# PS2_Regulators.net
KiCad netlist of a schematic drawn in Altium Designer
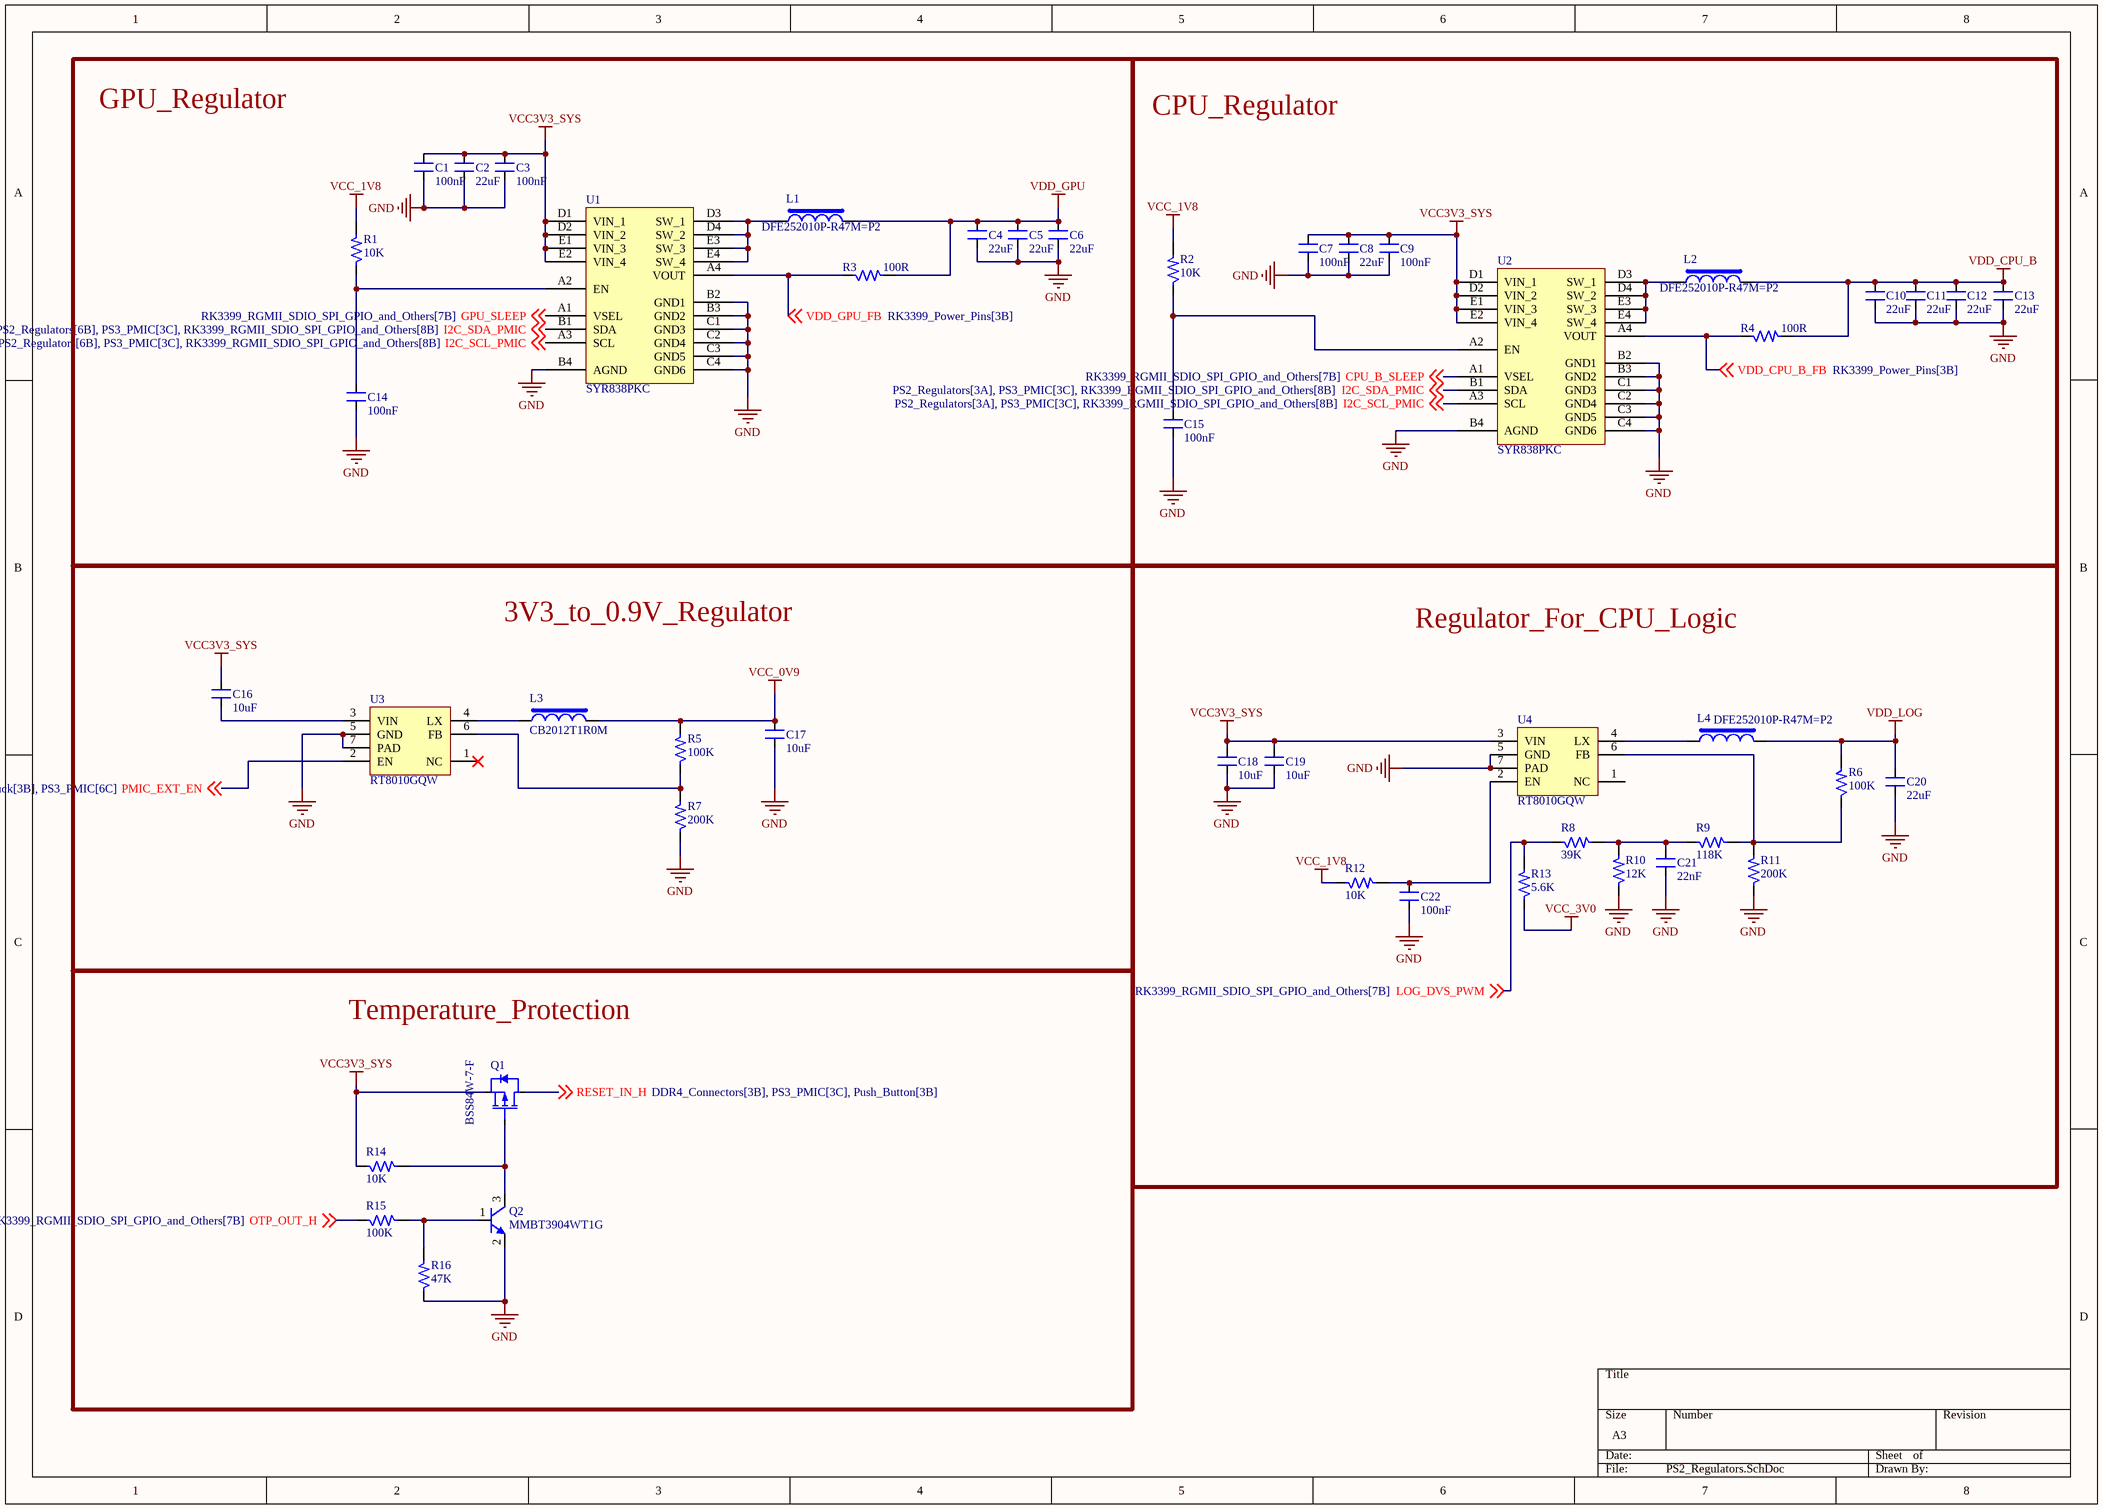
[diagram p0: PS2_Regulators.SchDoc]

(export (version "E")
  (design (tool "Eeschema 10.0.6"))
  (components
    (comp (ref "C1")
      (value "100nF")
      (footprint "CAP_0402")
      (description "0.1µF ±10% 25V Ceramic Capacitor X7R 0402 (1005 Metric)")
      (fields
        (field (name "MANUFACTURER") "Walsin Technology Corporation")
        (field (name "MANUFACTURER PART NUMBER") "0402B104K250CT")
      )
      (libsource (lib "EsteemPCB_SOM_Course_schlib") (part "CAP_100nF-25V-10%-0402"))
    )
    (comp (ref "C2")
      (value "22uF")
      (footprint "CAP_0603")
      (description "22µF ±20% 10V Ceramic Capacitor X5R 0603 (1608 Metric)")
      (fields
        (field (name "MANUFACTURER") "Murata Electronics")
        (field (name "MANUFACTURER PART NUMBER") "GRM188R61A226ME15D")
      )
      (libsource (lib "EsteemPCB_SOM_Course_schlib") (part "CAP_22uF-10V-20%-0603"))
    )
    (comp (ref "C3")
      (value "100nF")
      (footprint "CAP_0402")
      (description "0.1µF ±10% 25V Ceramic Capacitor X7R 0402 (1005 Metric)")
      (fields
        (field (name "MANUFACTURER") "Walsin Technology Corporation")
        (field (name "MANUFACTURER PART NUMBER") "0402B104K250CT")
      )
      (libsource (lib "EsteemPCB_SOM_Course_schlib") (part "CAP_100nF-25V-10%-0402"))
    )
    (comp (ref "C4")
      (value "22uF")
      (footprint "CAP_0603")
      (description "22µF ±20% 10V Ceramic Capacitor X5R 0603 (1608 Metric)")
      (fields
        (field (name "MANUFACTURER") "Murata Electronics")
        (field (name "MANUFACTURER PART NUMBER") "GRM188R61A226ME15D")
      )
      (libsource (lib "EsteemPCB_SOM_Course_schlib") (part "CAP_22uF-10V-20%-0603"))
    )
    (comp (ref "C5")
      (value "22uF")
      (footprint "CAP_0603")
      (description "22µF ±20% 10V Ceramic Capacitor X5R 0603 (1608 Metric)")
      (fields
        (field (name "MANUFACTURER") "Murata Electronics")
        (field (name "MANUFACTURER PART NUMBER") "GRM188R61A226ME15D")
      )
      (libsource (lib "EsteemPCB_SOM_Course_schlib") (part "CAP_22uF-10V-20%-0603"))
    )
    (comp (ref "C6")
      (value "22uF")
      (footprint "CAP_0603")
      (description "22µF ±20% 10V Ceramic Capacitor X5R 0603 (1608 Metric)")
      (fields
        (field (name "MANUFACTURER") "Murata Electronics")
        (field (name "MANUFACTURER PART NUMBER") "GRM188R61A226ME15D")
      )
      (libsource (lib "EsteemPCB_SOM_Course_schlib") (part "CAP_22uF-10V-20%-0603"))
    )
    (comp (ref "C7")
      (value "100nF")
      (footprint "CAP_0402")
      (description "0.1µF ±10% 25V Ceramic Capacitor X7R 0402 (1005 Metric)")
      (fields
        (field (name "MANUFACTURER") "Walsin Technology Corporation")
        (field (name "MANUFACTURER PART NUMBER") "0402B104K250CT")
      )
      (libsource (lib "EsteemPCB_SOM_Course_schlib") (part "CAP_100nF-25V-10%-0402"))
    )
    (comp (ref "C8")
      (value "22uF")
      (footprint "CAP_0603")
      (description "22µF ±20% 10V Ceramic Capacitor X5R 0603 (1608 Metric)")
      (fields
        (field (name "MANUFACTURER") "Murata Electronics")
        (field (name "MANUFACTURER PART NUMBER") "GRM188R61A226ME15D")
      )
      (libsource (lib "EsteemPCB_SOM_Course_schlib") (part "CAP_22uF-10V-20%-0603"))
    )
    (comp (ref "C9")
      (value "100nF")
      (footprint "CAP_0402")
      (description "0.1µF ±10% 25V Ceramic Capacitor X7R 0402 (1005 Metric)")
      (fields
        (field (name "MANUFACTURER") "Walsin Technology Corporation")
        (field (name "MANUFACTURER PART NUMBER") "0402B104K250CT")
      )
      (libsource (lib "EsteemPCB_SOM_Course_schlib") (part "CAP_100nF-25V-10%-0402"))
    )
    (comp (ref "C10")
      (value "22uF")
      (footprint "CAP_0603")
      (description "22µF ±20% 10V Ceramic Capacitor X5R 0603 (1608 Metric)")
      (fields
        (field (name "MANUFACTURER") "Murata Electronics")
        (field (name "MANUFACTURER PART NUMBER") "GRM188R61A226ME15D")
      )
      (libsource (lib "EsteemPCB_SOM_Course_schlib") (part "CAP_22uF-10V-20%-0603"))
    )
    (comp (ref "C11")
      (value "22uF")
      (footprint "CAP_0603")
      (description "22µF ±20% 10V Ceramic Capacitor X5R 0603 (1608 Metric)")
      (fields
        (field (name "MANUFACTURER") "Murata Electronics")
        (field (name "MANUFACTURER PART NUMBER") "GRM188R61A226ME15D")
      )
      (libsource (lib "EsteemPCB_SOM_Course_schlib") (part "CAP_22uF-10V-20%-0603"))
    )
    (comp (ref "C12")
      (value "22uF")
      (footprint "CAP_0603")
      (description "22µF ±20% 10V Ceramic Capacitor X5R 0603 (1608 Metric)")
      (fields
        (field (name "MANUFACTURER") "Murata Electronics")
        (field (name "MANUFACTURER PART NUMBER") "GRM188R61A226ME15D")
      )
      (libsource (lib "EsteemPCB_SOM_Course_schlib") (part "CAP_22uF-10V-20%-0603"))
    )
    (comp (ref "C13")
      (value "22uF")
      (footprint "CAP_0603")
      (description "22µF ±20% 10V Ceramic Capacitor X5R 0603 (1608 Metric)")
      (fields
        (field (name "MANUFACTURER") "Murata Electronics")
        (field (name "MANUFACTURER PART NUMBER") "GRM188R61A226ME15D")
      )
      (libsource (lib "EsteemPCB_SOM_Course_schlib") (part "CAP_22uF-10V-20%-0603"))
    )
    (comp (ref "C14")
      (value "100nF")
      (footprint "CAP_0402")
      (description "0.1µF ±10% 25V Ceramic Capacitor X7R 0402 (1005 Metric)")
      (fields
        (field (name "MANUFACTURER") "Walsin Technology Corporation")
        (field (name "MANUFACTURER PART NUMBER") "0402B104K250CT")
      )
      (libsource (lib "EsteemPCB_SOM_Course_schlib") (part "CAP_100nF-25V-10%-0402"))
    )
    (comp (ref "C15")
      (value "100nF")
      (footprint "CAP_0402")
      (description "0.1µF ±10% 25V Ceramic Capacitor X7R 0402 (1005 Metric)")
      (fields
        (field (name "MANUFACTURER") "Walsin Technology Corporation")
        (field (name "MANUFACTURER PART NUMBER") "0402B104K250CT")
      )
      (libsource (lib "EsteemPCB_SOM_Course_schlib") (part "CAP_100nF-25V-10%-0402"))
    )
    (comp (ref "C16")
      (value "10uF")
      (footprint "CAP_0402")
      (description "10µF ±20% 10V Ceramic Capacitor X5R 0402 (1005 Metric)")
      (fields
        (field (name "MANUFACTURER PART NUMBER") "CL05A106MP5NUNC")
        (field (name "MANUFACTURER") "Samsung Electro-Mechanics")
      )
      (libsource (lib "EsteemPCB_SOM_Course_schlib") (part "CAP_10uF-10V-20%-0402"))
    )
    (comp (ref "C17")
      (value "10uF")
      (footprint "CAP_0402")
      (description "10µF ±20% 10V Ceramic Capacitor X5R 0402 (1005 Metric)")
      (fields
        (field (name "MANUFACTURER PART NUMBER") "CL05A106MP5NUNC")
        (field (name "MANUFACTURER") "Samsung Electro-Mechanics")
      )
      (libsource (lib "EsteemPCB_SOM_Course_schlib") (part "CAP_10uF-10V-20%-0402"))
    )
    (comp (ref "C18")
      (value "10uF")
      (footprint "CAP_0402")
      (description "10µF ±20% 10V Ceramic Capacitor X5R 0402 (1005 Metric)")
      (fields
        (field (name "MANUFACTURER PART NUMBER") "CL05A106MP5NUNC")
        (field (name "MANUFACTURER") "Samsung Electro-Mechanics")
      )
      (libsource (lib "EsteemPCB_SOM_Course_schlib") (part "CAP_10uF-10V-20%-0402"))
    )
    (comp (ref "C19")
      (value "10uF")
      (footprint "CAP_0402")
      (description "10µF ±20% 10V Ceramic Capacitor X5R 0402 (1005 Metric)")
      (fields
        (field (name "MANUFACTURER PART NUMBER") "CL05A106MP5NUNC")
        (field (name "MANUFACTURER") "Samsung Electro-Mechanics")
      )
      (libsource (lib "EsteemPCB_SOM_Course_schlib") (part "CAP_10uF-10V-20%-0402"))
    )
    (comp (ref "C20")
      (value "22uF")
      (footprint "CAP_0603")
      (description "22µF ±20% 10V Ceramic Capacitor X5R 0603 (1608 Metric)")
      (fields
        (field (name "MANUFACTURER") "Murata Electronics")
        (field (name "MANUFACTURER PART NUMBER") "GRM188R61A226ME15D")
      )
      (libsource (lib "EsteemPCB_SOM_Course_schlib") (part "CAP_22uF-10V-20%-0603"))
    )
    (comp (ref "C21")
      (value "22nF")
      (footprint "CAP_0402")
      (description "0.022µF ±10% 10V Ceramic Capacitor X7R 0402 (1005 Metric)")
      (fields
        (field (name "MANUFACTURER") "Samsung Electro-Mechanics")
        (field (name "MANUFACTURER PART NUMBER") "CL05B223KP5NNNC")
      )
      (libsource (lib "EsteemPCB_SOM_Course_schlib") (part "CAP_22nF-10V-10%-0402"))
    )
    (comp (ref "C22")
      (value "100nF")
      (footprint "CAP_0402")
      (description "0.1µF ±10% 25V Ceramic Capacitor X7R 0402 (1005 Metric)")
      (fields
        (field (name "MANUFACTURER") "Walsin Technology Corporation")
        (field (name "MANUFACTURER PART NUMBER") "0402B104K250CT")
      )
      (libsource (lib "EsteemPCB_SOM_Course_schlib") (part "CAP_100nF-25V-10%-0402"))
    )
    (comp (ref "L1")
      (value "DFE252010P-R47M=P2")
      (footprint "IND_1008")
      (description "470nH Shielded Wirewound Inductor 5A 35mOhm Max 1008 (2520 Metric)")
      (fields (field (name "MANUFACTURER") "Murata Electronics"))
      (libsource (lib "EsteemPCB_SOM_Course_schlib") (part "IND_470nH-5A-20%-1008"))
    )
    (comp (ref "L2")
      (value "DFE252010P-R47M=P2")
      (footprint "IND_1008")
      (description "470nH Shielded Wirewound Inductor 5A 35mOhm Max 1008 (2520 Metric)")
      (fields (field (name "MANUFACTURER") "Murata Electronics"))
      (libsource (lib "EsteemPCB_SOM_Course_schlib") (part "IND_470nH-5A-20%-1008"))
    )
    (comp (ref "L3")
      (value "CB2012T1R0M")
      (footprint "IND_0805")
      (description "1uH ±20% 500mA 150mΩ 0805 Inductors (SMD) RoHS")
      (fields (field (name "MANUFACTURER") "Taiyo Yuden"))
      (libsource (lib "EsteemPCB_SOM_Course_schlib") (part "IND_1uF-0.5A-20%-0805"))
    )
    (comp (ref "L4")
      (value "DFE252010P-R47M=P2")
      (footprint "IND_1008")
      (description "470nH Shielded Wirewound Inductor 5A 35mOhm Max 1008 (2520 Metric)")
      (fields (field (name "MANUFACTURER") "Murata Electronics"))
      (libsource (lib "EsteemPCB_SOM_Course_schlib") (part "IND_470nH-5A-20%-1008"))
    )
    (comp (ref "Q1")
      (value "BSS84W-7-F")
      (footprint "SOT-323-3")
      (description "P-Channel 50V 130mA (Ta) 200mW (Ta) Surface Mount SOT-323")
      (fields (field (name "MANUFACTURER") "Diodes Incorporated"))
      (libsource (lib "EsteemPCB_SOM_Course_schlib") (part "MOSFET-P_50V-130mA-SOT-323"))
    )
    (comp (ref "Q2")
      (value "MMBT3904WT1G")
      (footprint "SOT-323-3")
      (description "Bipolar Transistors - BJT 200mA 60V NPN")
      (fields (field (name "MANUFACTURER") "ON Semiconductor"))
      (libsource (lib "EsteemPCB_SOM_Course_schlib") (part "TRNS-NPN_60V-0.2A-SOT323"))
    )
    (comp (ref "R1")
      (value "10K")
      (footprint "RES_0402")
      (description "10 kOhms ±1% 0.1W, 1/10W Chip Resistor 0402 (1005 Metric) Anti-Sulfur Thin Film")
      (fields
        (field (name "MANUFACTURER") "Vishay Beyschlag/Draloric/BC Components")
        (field (name "MANUFACTURER PART NUMBER") "MCS04020C1002FE000")
      )
      (libsource (lib "EsteemPCB_SOM_Course_schlib") (part "RES_10K-0.1W-1%-0402"))
    )
    (comp (ref "R2")
      (value "10K")
      (footprint "RES_0402")
      (description "10 kOhms ±1% 0.1W, 1/10W Chip Resistor 0402 (1005 Metric) Anti-Sulfur Thin Film")
      (fields
        (field (name "MANUFACTURER") "Vishay Beyschlag/Draloric/BC Components")
        (field (name "MANUFACTURER PART NUMBER") "MCS04020C1002FE000")
      )
      (libsource (lib "EsteemPCB_SOM_Course_schlib") (part "RES_10K-0.1W-1%-0402"))
    )
    (comp (ref "R3")
      (value "100R")
      (footprint "RES_0402")
      (fields
        (field (name "MANUFACTURER") "KOA Speer Electronics, Inc.")
        (field (name "MANUFACTURER PART NUMBER") "RK73H1ETTP1000F")
      )
      (libsource (lib "EsteemPCB_SOM_Course_schlib") (part "RES_100R-0.1W-1%-0402"))
    )
    (comp (ref "R4")
      (value "100R")
      (footprint "RES_0402")
      (fields
        (field (name "MANUFACTURER") "KOA Speer Electronics, Inc.")
        (field (name "MANUFACTURER PART NUMBER") "RK73H1ETTP1000F")
      )
      (libsource (lib "EsteemPCB_SOM_Course_schlib") (part "RES_100R-0.1W-1%-0402"))
    )
    (comp (ref "R5")
      (value "100K")
      (footprint "RES_0402")
      (description "100 kOhms ±1% 0.1W, 1/10W Chip Resistor 0402 (1005 Metric) Anti-Sulfur Thin Film")
      (fields
        (field (name "MANUFACTURER") "Vishay Beyschlag/Draloric/BC Components")
        (field (name "MANUFACTURER PART NUMBER") "MCS04020C1003FE000")
      )
      (libsource (lib "EsteemPCB_SOM_Course_schlib") (part "RES_100K-0.1W-1%-0402"))
    )
    (comp (ref "R6")
      (value "100K")
      (footprint "RES_0402")
      (description "100 kOhms ±1% 0.1W, 1/10W Chip Resistor 0402 (1005 Metric) Anti-Sulfur Thin Film")
      (fields
        (field (name "MANUFACTURER") "Vishay Beyschlag/Draloric/BC Components")
        (field (name "MANUFACTURER PART NUMBER") "MCS04020C1003FE000")
      )
      (libsource (lib "EsteemPCB_SOM_Course_schlib") (part "RES_100K-0.1W-1%-0402"))
    )
    (comp (ref "R7")
      (value "200K")
      (footprint "RES_0402")
      (description "200 kOhms ±1% 0.1W, 1/10W Chip Resistor 0402 (1005 Metric) Automotive AEC-Q200 Thick Film")
      (fields
        (field (name "MANUFACTURER") "Panasonic Electronic Components")
        (field (name "MANUFACTURER PART NUMBER") "ERJ-2RKF2003X")
      )
      (libsource (lib "EsteemPCB_SOM_Course_schlib") (part "RES_200K-0.1W-1%-0402"))
    )
    (comp (ref "R8")
      (value "39K")
      (footprint "RES_0402")
      (fields
        (field (name "MANUFACTURER") "KOA Speer Electronics, Inc.")
        (field (name "MANUFACTURER PART NUMBER") "RK73H1ETTP3902F")
      )
      (libsource (lib "EsteemPCB_SOM_Course_schlib") (part "RES_39K-0.1W-1%-0402"))
    )
    (comp (ref "R9")
      (value "118K")
      (footprint "RES_0402")
      (fields
        (field (name "MANUFACTURER") "KOA Speer Electronics, Inc.")
        (field (name "MANUAFCTURER PART NUMBER") "RK73H1ETTP1183F")
      )
      (libsource (lib "EsteemPCB_SOM_Course_schlib") (part "RES_118K-0.1W-1%-0402"))
    )
    (comp (ref "R10")
      (value "12K")
      (footprint "RES_0402")
      (description "12 kOhms ±1% 0.1W, 1/10W Chip Resistor 0402 (1005 Metric) Anti-Sulfur Thin Film")
      (fields
        (field (name "MANUFACTURER") "Vishay Beyschlag/Draloric/BC Components")
        (field (name "MANUFACTURER PART NUMBER") "MCS04020C1202FE000")
      )
      (libsource (lib "EsteemPCB_SOM_Course_schlib") (part "RES_12K-0.1W-1%-0402"))
    )
    (comp (ref "R11")
      (value "200K")
      (footprint "RES_0402")
      (description "200 kOhms ±1% 0.1W, 1/10W Chip Resistor 0402 (1005 Metric) Automotive AEC-Q200 Thick Film")
      (fields
        (field (name "MANUFACTURER") "Panasonic Electronic Components")
        (field (name "MANUFACTURER PART NUMBER") "ERJ-2RKF2003X")
      )
      (libsource (lib "EsteemPCB_SOM_Course_schlib") (part "RES_200K-0.1W-1%-0402"))
    )
    (comp (ref "R12")
      (value "10K")
      (footprint "RES_0402")
      (description "10 kOhms ±1% 0.1W, 1/10W Chip Resistor 0402 (1005 Metric) Anti-Sulfur Thin Film")
      (fields
        (field (name "MANUFACTURER") "Vishay Beyschlag/Draloric/BC Components")
        (field (name "MANUFACTURER PART NUMBER") "MCS04020C1002FE000")
      )
      (libsource (lib "EsteemPCB_SOM_Course_schlib") (part "RES_10K-0.1W-1%-0402"))
    )
    (comp (ref "R13")
      (value "5.6K")
      (footprint "RES_0402")
      (fields
        (field (name "MANUFACTURER") "KOA Speer Electronics, Inc.")
        (field (name "MANUFACTURER PART NUMBER") "RK73H1ETTP5601F")
      )
      (libsource (lib "EsteemPCB_SOM_Course_schlib") (part "RES_5.6K-0.1W-1%-0402"))
    )
    (comp (ref "R14")
      (value "10K")
      (footprint "RES_0402")
      (description "10 kOhms ±1% 0.1W, 1/10W Chip Resistor 0402 (1005 Metric) Anti-Sulfur Thin Film")
      (fields
        (field (name "MANUFACTURER") "Vishay Beyschlag/Draloric/BC Components")
        (field (name "MANUFACTURER PART NUMBER") "MCS04020C1002FE000")
      )
      (libsource (lib "EsteemPCB_SOM_Course_schlib") (part "RES_10K-0.1W-1%-0402"))
    )
    (comp (ref "R15")
      (value "100K")
      (footprint "RES_0402")
      (description "100 kOhms ±1% 0.1W, 1/10W Chip Resistor 0402 (1005 Metric) Anti-Sulfur Thin Film")
      (fields
        (field (name "MANUFACTURER") "Vishay Beyschlag/Draloric/BC Components")
        (field (name "MANUFACTURER PART NUMBER") "MCS04020C1003FE000")
      )
      (libsource (lib "EsteemPCB_SOM_Course_schlib") (part "RES_100K-0.1W-1%-0402"))
    )
    (comp (ref "R16")
      (value "47K")
      (footprint "RES_0402")
      (description "47 kOhms ±1% 0.1W, 1/10W Chip Resistor 0402 (1005 Metric) Automotive AEC-Q200 Thick Film")
      (fields
        (field (name "MANUFACTURER") "Panasonic Electronic Components")
        (field (name "MANUFACTURER PART NUMBER") "ERJ-2RKF4702X")
      )
      (libsource (lib "EsteemPCB_SOM_Course_schlib") (part "RES_47K-0.1W-1%-0402"))
    )
    (comp (ref "U1")
      (value "SYR838PKC")
      (footprint "CSP20_15.7_100x84_SMD")
      (description "Step-Down Positive Programmable 1 6A 2.4MHz CSP1.56*1.96-20 DC-DC Converters RoHS")
      (fields (field (name "MANUFACTURER") "Silergy Corp"))
      (libsource (lib "EsteemPCB_SOM_Course_schlib") (part "IC_SYR838PKC"))
    )
    (comp (ref "U2")
      (value "SYR838PKC")
      (footprint "CSP20_15.7_100x84_SMD")
      (description "Step-Down Positive Programmable 1 6A 2.4MHz CSP1.56*1.96-20 DC-DC Converters RoHS")
      (fields (field (name "MANUFACTURER") "Silergy Corp"))
      (libsource (lib "EsteemPCB_SOM_Course_schlib") (part "IC_SYR838PKC"))
    )
    (comp (ref "U3")
      (value "RT8010GQW")
      (footprint "WDFN-6_26_133X100_SMD")
      (description "Buck Switching Regulator IC Positive Adjustable 0.6V 1 Output 1A 6-WDFN Exposed Pad")
      (fields (field (name "MANUFACTURER") "Richtek USA Inc."))
      (libsource (lib "EsteemPCB_SOM_Course_schlib") (part "REG-ADJ_5.5V-5.5V-1A-6-WDFN"))
    )
    (comp (ref "U4")
      (value "RT8010GQW")
      (footprint "WDFN-6_26_133X100_SMD")
      (description "Buck Switching Regulator IC Positive Adjustable 0.6V 1 Output 1A 6-WDFN Exposed Pad")
      (fields (field (name "MANUFACTURER") "Richtek USA Inc."))
      (libsource (lib "EsteemPCB_SOM_Course_schlib") (part "REG-ADJ_5.5V-5.5V-1A-6-WDFN"))
    )
  )
  (nets
    (net (code "1") (name "CPU_B_SLEEP") (class "Default")
      (node (ref "U2") (pin "A1") (pinfunction "VSEL_A1") (pintype "passive"))
    )
    (net (code "2") (name "GND") (class "Default")
      (node (ref "C1") (pin "1") (pinfunction "1_1") (pintype "passive"))
      (node (ref "C10") (pin "1") (pinfunction "1_1") (pintype "passive"))
      (node (ref "C11") (pin "1") (pinfunction "1_1") (pintype "passive"))
      (node (ref "C12") (pin "1") (pinfunction "1_1") (pintype "passive"))
      (node (ref "C13") (pin "1") (pinfunction "1_1") (pintype "passive"))
      (node (ref "C14") (pin "1") (pinfunction "1_1") (pintype "passive"))
      (node (ref "C15") (pin "1") (pinfunction "1_1") (pintype "passive"))
      (node (ref "C17") (pin "1") (pinfunction "1_1") (pintype "passive"))
      (node (ref "C18") (pin "1") (pinfunction "1_1") (pintype "passive"))
      (node (ref "C19") (pin "1") (pinfunction "1_1") (pintype "passive"))
      (node (ref "C2") (pin "1") (pinfunction "1_1") (pintype "passive"))
      (node (ref "C20") (pin "1") (pinfunction "1_1") (pintype "passive"))
      (node (ref "C21") (pin "1") (pinfunction "1_1") (pintype "passive"))
      (node (ref "C22") (pin "1") (pinfunction "1_1") (pintype "passive"))
      (node (ref "C3") (pin "1") (pinfunction "1_1") (pintype "passive"))
      (node (ref "C4") (pin "1") (pinfunction "1_1") (pintype "passive"))
      (node (ref "C5") (pin "1") (pinfunction "1_1") (pintype "passive"))
      (node (ref "C6") (pin "1") (pinfunction "1_1") (pintype "passive"))
      (node (ref "C7") (pin "1") (pinfunction "1_1") (pintype "passive"))
      (node (ref "C8") (pin "1") (pinfunction "1_1") (pintype "passive"))
      (node (ref "C9") (pin "1") (pinfunction "1_1") (pintype "passive"))
      (node (ref "Q2") (pin "2") (pinfunction "E_2") (pintype "passive"))
      (node (ref "R10") (pin "1") (pinfunction "1_1") (pintype "passive"))
      (node (ref "R11") (pin "1") (pinfunction "1_1") (pintype "passive"))
      (node (ref "R16") (pin "1") (pinfunction "1_1") (pintype "passive"))
      (node (ref "R7") (pin "1") (pinfunction "1_1") (pintype "passive"))
      (node (ref "U1") (pin "B2") (pinfunction "GND1_B2") (pintype "passive"))
      (node (ref "U1") (pin "B3") (pinfunction "GND2_B3") (pintype "passive"))
      (node (ref "U1") (pin "B4") (pinfunction "AGND_B4") (pintype "passive"))
      (node (ref "U1") (pin "C1") (pinfunction "GND3_C1") (pintype "passive"))
      (node (ref "U1") (pin "C2") (pinfunction "GND4_C2") (pintype "passive"))
      (node (ref "U1") (pin "C3") (pinfunction "GND5_C3") (pintype "passive"))
      (node (ref "U1") (pin "C4") (pinfunction "GND6_C4") (pintype "passive"))
      (node (ref "U2") (pin "B2") (pinfunction "GND1_B2") (pintype "passive"))
      (node (ref "U2") (pin "B3") (pinfunction "GND2_B3") (pintype "passive"))
      (node (ref "U2") (pin "B4") (pinfunction "AGND_B4") (pintype "passive"))
      (node (ref "U2") (pin "C1") (pinfunction "GND3_C1") (pintype "passive"))
      (node (ref "U2") (pin "C2") (pinfunction "GND4_C2") (pintype "passive"))
      (node (ref "U2") (pin "C3") (pinfunction "GND5_C3") (pintype "passive"))
      (node (ref "U2") (pin "C4") (pinfunction "GND6_C4") (pintype "passive"))
      (node (ref "U3") (pin "5") (pinfunction "GND_5") (pintype "passive"))
      (node (ref "U3") (pin "7") (pinfunction "PAD_7") (pintype "passive"))
      (node (ref "U4") (pin "5") (pinfunction "GND_5") (pintype "passive"))
      (node (ref "U4") (pin "7") (pinfunction "PAD_7") (pintype "passive"))
    )
    (net (code "3") (name "GPU_SLEEP") (class "Default")
      (node (ref "U1") (pin "A1") (pinfunction "VSEL_A1") (pintype "passive"))
    )
    (net (code "4") (name "I2C_SCL_PMIC") (class "Default")
      (node (ref "U1") (pin "A3") (pinfunction "SCL_A3") (pintype "passive"))
      (node (ref "U2") (pin "A3") (pinfunction "SCL_A3") (pintype "passive"))
    )
    (net (code "5") (name "I2C_SDA_PMIC") (class "Default")
      (node (ref "U1") (pin "B1") (pinfunction "SDA_B1") (pintype "passive"))
      (node (ref "U2") (pin "B1") (pinfunction "SDA_B1") (pintype "passive"))
    )
    (net (code "6") (name "LOG_DVS_PWM") (class "Default")
      (node (ref "R13") (pin "2") (pinfunction "2_2") (pintype "passive"))
      (node (ref "R8") (pin "1") (pinfunction "1_1") (pintype "passive"))
    )
    (net (code "7") (name "Net-(C21-Pad2)") (class "Default")
      (node (ref "C21") (pin "2") (pinfunction "2_2") (pintype "passive"))
      (node (ref "R10") (pin "2") (pinfunction "2_2") (pintype "passive"))
      (node (ref "R8") (pin "2") (pinfunction "2_2") (pintype "passive"))
      (node (ref "R9") (pin "1") (pinfunction "1_1") (pintype "passive"))
    )
    (net (code "8") (name "Net-(Q1-G)") (class "Default")
      (node (ref "Q1") (pin "1") (pinfunction "G_1") (pintype "passive"))
      (node (ref "Q2") (pin "3") (pinfunction "C_3") (pintype "passive"))
      (node (ref "R14") (pin "2") (pinfunction "2_2") (pintype "passive"))
    )
    (net (code "9") (name "Net-(Q2-B)") (class "Default")
      (node (ref "Q2") (pin "1") (pinfunction "B_1") (pintype "passive"))
      (node (ref "R15") (pin "2") (pinfunction "2_2") (pintype "passive"))
      (node (ref "R16") (pin "2") (pinfunction "2_2") (pintype "passive"))
    )
    (net (code "10") (name "Net-(U1-EN)") (class "Default")
      (node (ref "C14") (pin "2") (pinfunction "2_2") (pintype "passive"))
      (node (ref "R1") (pin "1") (pinfunction "1_1") (pintype "passive"))
      (node (ref "U1") (pin "A2") (pinfunction "EN_A2") (pintype "passive"))
    )
    (net (code "11") (name "Net-(U1-SW_1)") (class "Default")
      (node (ref "L1") (pin "1") (pinfunction "1_1") (pintype "passive"))
      (node (ref "U1") (pin "D3") (pinfunction "SW_1_D3") (pintype "passive"))
      (node (ref "U1") (pin "D4") (pinfunction "SW_2_D4") (pintype "passive"))
      (node (ref "U1") (pin "E3") (pinfunction "SW_3_E3") (pintype "passive"))
      (node (ref "U1") (pin "E4") (pinfunction "SW_4_E4") (pintype "passive"))
    )
    (net (code "12") (name "Net-(U2-EN)") (class "Default")
      (node (ref "C15") (pin "2") (pinfunction "2_2") (pintype "passive"))
      (node (ref "R2") (pin "1") (pinfunction "1_1") (pintype "passive"))
      (node (ref "U2") (pin "A2") (pinfunction "EN_A2") (pintype "passive"))
    )
    (net (code "13") (name "Net-(U2-SW_1)") (class "Default")
      (node (ref "L2") (pin "1") (pinfunction "1_1") (pintype "passive"))
      (node (ref "U2") (pin "D3") (pinfunction "SW_1_D3") (pintype "passive"))
      (node (ref "U2") (pin "D4") (pinfunction "SW_2_D4") (pintype "passive"))
      (node (ref "U2") (pin "E3") (pinfunction "SW_3_E3") (pintype "passive"))
      (node (ref "U2") (pin "E4") (pinfunction "SW_4_E4") (pintype "passive"))
    )
    (net (code "14") (name "Net-(U3-FB)") (class "Default")
      (node (ref "R5") (pin "1") (pinfunction "1_1") (pintype "passive"))
      (node (ref "R7") (pin "2") (pinfunction "2_2") (pintype "passive"))
      (node (ref "U3") (pin "6") (pinfunction "FB_6") (pintype "passive"))
    )
    (net (code "15") (name "Net-(U3-LX)") (class "Default")
      (node (ref "L3") (pin "1") (pinfunction "1_1") (pintype "passive"))
      (node (ref "U3") (pin "4") (pinfunction "LX_4") (pintype "passive"))
    )
    (net (code "16") (name "Net-(U3-VIN)") (class "Default")
      (node (ref "C16") (pin "1") (pinfunction "1_1") (pintype "passive"))
      (node (ref "U3") (pin "3") (pinfunction "VIN_3") (pintype "passive"))
    )
    (net (code "17") (name "Net-(U4-EN)") (class "Default")
      (node (ref "C22") (pin "2") (pinfunction "2_2") (pintype "passive"))
      (node (ref "R12") (pin "2") (pinfunction "2_2") (pintype "passive"))
      (node (ref "U4") (pin "2") (pinfunction "EN_2") (pintype "passive"))
    )
    (net (code "18") (name "Net-(U4-FB)") (class "Default")
      (node (ref "R11") (pin "2") (pinfunction "2_2") (pintype "passive"))
      (node (ref "R6") (pin "1") (pinfunction "1_1") (pintype "passive"))
      (node (ref "R9") (pin "2") (pinfunction "2_2") (pintype "passive"))
      (node (ref "U4") (pin "6") (pinfunction "FB_6") (pintype "passive"))
    )
    (net (code "19") (name "Net-(U4-LX)") (class "Default")
      (node (ref "L4") (pin "1") (pinfunction "1_1") (pintype "passive"))
      (node (ref "U4") (pin "4") (pinfunction "LX_4") (pintype "passive"))
    )
    (net (code "20") (name "OTP_OUT_H") (class "Default")
      (node (ref "R15") (pin "1") (pinfunction "1_1") (pintype "passive"))
    )
    (net (code "21") (name "PMIC_EXT_EN") (class "Default")
      (node (ref "U3") (pin "2") (pinfunction "EN_2") (pintype "passive"))
    )
    (net (code "22") (name "RESET_IN_H") (class "Default")
      (node (ref "Q1") (pin "3") (pinfunction "D_3") (pintype "passive"))
    )
    (net (code "23") (name "VCC3V3_SYS") (class "Default")
      (node (ref "C1") (pin "2") (pinfunction "2_2") (pintype "passive"))
      (node (ref "C16") (pin "2") (pinfunction "2_2") (pintype "passive"))
      (node (ref "C18") (pin "2") (pinfunction "2_2") (pintype "passive"))
      (node (ref "C19") (pin "2") (pinfunction "2_2") (pintype "passive"))
      (node (ref "C2") (pin "2") (pinfunction "2_2") (pintype "passive"))
      (node (ref "C3") (pin "2") (pinfunction "2_2") (pintype "passive"))
      (node (ref "C7") (pin "2") (pinfunction "2_2") (pintype "passive"))
      (node (ref "C8") (pin "2") (pinfunction "2_2") (pintype "passive"))
      (node (ref "C9") (pin "2") (pinfunction "2_2") (pintype "passive"))
      (node (ref "Q1") (pin "2") (pinfunction "S_2") (pintype "passive"))
      (node (ref "R14") (pin "1") (pinfunction "1_1") (pintype "passive"))
      (node (ref "U1") (pin "D1") (pinfunction "VIN_1_D1") (pintype "passive"))
      (node (ref "U1") (pin "D2") (pinfunction "VIN_2_D2") (pintype "passive"))
      (node (ref "U1") (pin "E1") (pinfunction "VIN_3_E1") (pintype "passive"))
      (node (ref "U1") (pin "E2") (pinfunction "VIN_4_E2") (pintype "passive"))
      (node (ref "U2") (pin "D1") (pinfunction "VIN_1_D1") (pintype "passive"))
      (node (ref "U2") (pin "D2") (pinfunction "VIN_2_D2") (pintype "passive"))
      (node (ref "U2") (pin "E1") (pinfunction "VIN_3_E1") (pintype "passive"))
      (node (ref "U2") (pin "E2") (pinfunction "VIN_4_E2") (pintype "passive"))
      (node (ref "U4") (pin "3") (pinfunction "VIN_3") (pintype "passive"))
    )
    (net (code "24") (name "VCC_0V9") (class "Default")
      (node (ref "C17") (pin "2") (pinfunction "2_2") (pintype "passive"))
      (node (ref "L3") (pin "2") (pinfunction "2_2") (pintype "passive"))
      (node (ref "R5") (pin "2") (pinfunction "2_2") (pintype "passive"))
    )
    (net (code "25") (name "VCC_1V8") (class "Default")
      (node (ref "R1") (pin "2") (pinfunction "2_2") (pintype "passive"))
      (node (ref "R12") (pin "1") (pinfunction "1_1") (pintype "passive"))
      (node (ref "R2") (pin "2") (pinfunction "2_2") (pintype "passive"))
    )
    (net (code "26") (name "VCC_3V0") (class "Default")
      (node (ref "R13") (pin "1") (pinfunction "1_1") (pintype "passive"))
    )
    (net (code "27") (name "VDD_CPU_B") (class "Default")
      (node (ref "C10") (pin "2") (pinfunction "2_2") (pintype "passive"))
      (node (ref "C11") (pin "2") (pinfunction "2_2") (pintype "passive"))
      (node (ref "C12") (pin "2") (pinfunction "2_2") (pintype "passive"))
      (node (ref "C13") (pin "2") (pinfunction "2_2") (pintype "passive"))
      (node (ref "L2") (pin "2") (pinfunction "2_2") (pintype "passive"))
      (node (ref "R4") (pin "2") (pinfunction "2_2") (pintype "passive"))
    )
    (net (code "28") (name "VDD_CPU_B_FB") (class "Default")
      (node (ref "R4") (pin "1") (pinfunction "1_1") (pintype "passive"))
      (node (ref "U2") (pin "A4") (pinfunction "VOUT_A4") (pintype "passive"))
    )
    (net (code "29") (name "VDD_GPU") (class "Default")
      (node (ref "C4") (pin "2") (pinfunction "2_2") (pintype "passive"))
      (node (ref "C5") (pin "2") (pinfunction "2_2") (pintype "passive"))
      (node (ref "C6") (pin "2") (pinfunction "2_2") (pintype "passive"))
      (node (ref "L1") (pin "2") (pinfunction "2_2") (pintype "passive"))
      (node (ref "R3") (pin "2") (pinfunction "2_2") (pintype "passive"))
    )
    (net (code "30") (name "VDD_GPU_FB") (class "Default")
      (node (ref "R3") (pin "1") (pinfunction "1_1") (pintype "passive"))
      (node (ref "U1") (pin "A4") (pinfunction "VOUT_A4") (pintype "passive"))
    )
    (net (code "31") (name "VDD_LOG") (class "Default")
      (node (ref "C20") (pin "2") (pinfunction "2_2") (pintype "passive"))
      (node (ref "L4") (pin "2") (pinfunction "2_2") (pintype "passive"))
      (node (ref "R6") (pin "2") (pinfunction "2_2") (pintype "passive"))
    )
    (net (code "32") (name "unconnected-(U3-NC-Pad1)") (class "Default")
      (node (ref "U3") (pin "1") (pinfunction "NC_1") (pintype "passive+no_connect"))
    )
    (net (code "33") (name "unconnected-(U4-NC-Pad1)") (class "Default")
      (node (ref "U4") (pin "1") (pinfunction "NC_1") (pintype "passive"))
    )
  )
)
